# OC_PROT.net
KiCad netlist of a schematic drawn in Altium Designer
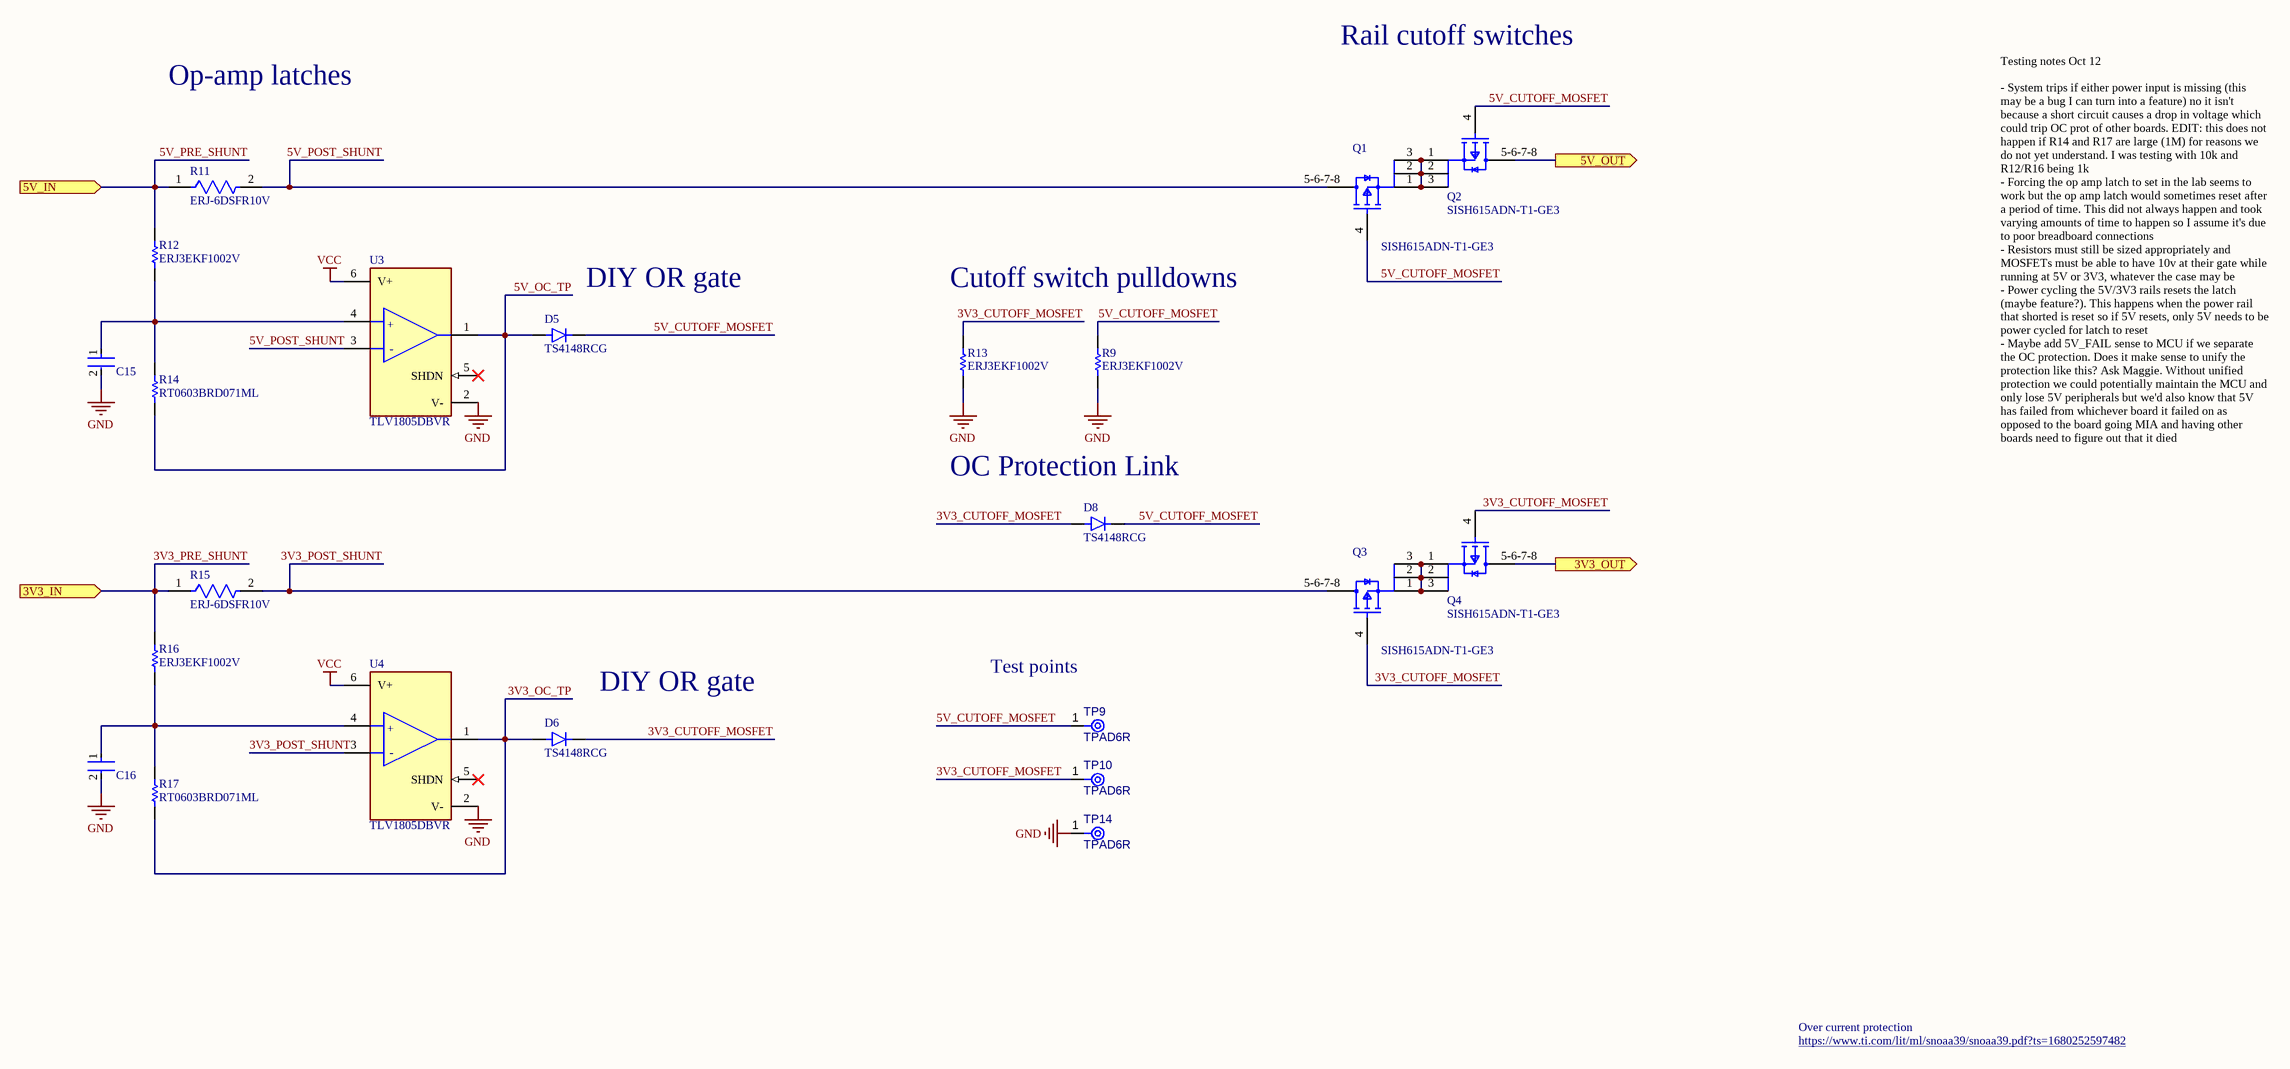
[diagram p0: OC_PROT.SchDoc]

(export (version "E")
  (design (tool "Eeschema 10.0.6"))
  (components
    (comp (ref "C15")
      (value "C0402C104K8PACTU")
      (footprint "FP-C0402-BB-MFG")
      (description "CAP CER 0.1UF 10V X5R 0402")
      (fields (field (name "MANUFACTURER") "Kemet") (field (name "TOLERANCE") "0.1"))
      (libsource (lib "Altium Content Vault") (part "b4654b650e69147ec39a6b967a45e02"))
    )
    (comp (ref "C16")
      (value "C0402C104K8PACTU")
      (footprint "FP-C0402-BB-MFG")
      (description "CAP CER 0.1UF 10V X5R 0402")
      (fields (field (name "MANUFACTURER") "Kemet") (field (name "TOLERANCE") "0.1"))
      (libsource (lib "Altium Content Vault") (part "b4654b650e69147ec39a6b967a45e02"))
    )
    (comp (ref "D5")
      (value "TS4148RCG")
      (footprint "TS4148RCG-Footprint-1")
      (description "SMD Si-Diode 75V 100mA 0603")
      (libsource (lib "uORocketry Hardware") (part "TS4148RCG"))
    )
    (comp (ref "D6")
      (value "TS4148RCG")
      (footprint "TS4148RCG-Footprint-1")
      (description "SMD Si-Diode 75V 100mA 0603")
      (libsource (lib "uORocketry Hardware") (part "TS4148RCG"))
    )
    (comp (ref "D8")
      (value "TS4148RCG")
      (footprint "TS4148RCG-Footprint-1")
      (description "SMD Si-Diode 75V 100mA 0603")
      (libsource (lib "uORocketry Hardware") (part "TS4148RCG"))
    )
    (comp (ref "Q1")
      (value "SISH615ADN-T1-GE3")
      (footprint "SISH615ADN-T1-GE3-Footprint-1")
      (description "Trans MOSFET P-CH 20V 22.1A 8-Pin PowerPAK 1212 EP T/R")
      (libsource (lib "uORocketry Hardware") (part "SISH615ADN-T1-GE3-Symbol-1"))
    )
    (comp (ref "Q2")
      (value "SISH615ADN-T1-GE3")
      (footprint "SISH615ADN-T1-GE3-Footprint-1")
      (description "Trans MOSFET P-CH 20V 22.1A 8-Pin PowerPAK 1212 EP T/R")
      (libsource (lib "uORocketry Hardware") (part "SISH615ADN-T1-GE3-Symbol-1"))
    )
    (comp (ref "Q3")
      (value "SISH615ADN-T1-GE3")
      (footprint "SISH615ADN-T1-GE3-Footprint-1")
      (description "Trans MOSFET P-CH 20V 22.1A 8-Pin PowerPAK 1212 EP T/R")
      (libsource (lib "uORocketry Hardware") (part "SISH615ADN-T1-GE3-Symbol-1"))
    )
    (comp (ref "Q4")
      (value "SISH615ADN-T1-GE3")
      (footprint "SISH615ADN-T1-GE3-Footprint-1")
      (description "Trans MOSFET P-CH 20V 22.1A 8-Pin PowerPAK 1212 EP T/R")
      (libsource (lib "uORocketry Hardware") (part "SISH615ADN-T1-GE3-Symbol-1"))
    )
    (comp (ref "R9")
      (value "ERJ3EKF1002V")
      (footprint "RESC1609X55X30LL15T15")
      (description "Chip Resistor, 10 KOhm, +/- 1%, 0.1 W, -55 to 155 degC, 0603 (1608 Metric), RoHS, Tape and Reel")
      (fields (field (name "TOLERANCE") "1%") (field (name "MANUFACTURER") "Panasonic"))
      (libsource (lib "Altium Content Vault") (part "RES-2"))
    )
    (comp (ref "R11")
      (value "ERJ-6DSFR10V")
      (footprint "FP-ERJ6D-MFG")
      (description "RES 0.1 OHM 1% 1/2W 0805")
      (fields (field (name "TOLERANCE") "1%"))
      (libsource (lib "Altium Content Vault") (part "1029c3af85768c4190bb7ad29bc67b5"))
    )
    (comp (ref "R12")
      (value "ERJ3EKF1002V")
      (footprint "RESC1609X55X30LL15T15")
      (description "Chip Resistor, 10 KOhm, +/- 1%, 0.1 W, -55 to 155 degC, 0603 (1608 Metric), RoHS, Tape and Reel")
      (fields (field (name "TOLERANCE") "1%") (field (name "MANUFACTURER") "Panasonic"))
      (libsource (lib "Altium Content Vault") (part "RES-2"))
    )
    (comp (ref "R13")
      (value "ERJ3EKF1002V")
      (footprint "RESC1609X55X30LL15T15")
      (description "Chip Resistor, 10 KOhm, +/- 1%, 0.1 W, -55 to 155 degC, 0603 (1608 Metric), RoHS, Tape and Reel")
      (fields (field (name "TOLERANCE") "1%") (field (name "MANUFACTURER") "Panasonic"))
      (libsource (lib "Altium Content Vault") (part "RES-2"))
    )
    (comp (ref "R14")
      (value "RT0603BRD071ML")
      (footprint "RESC1608X55X30NL20T20")
      (fields (field (name "MANUFACTURER") "Panasonic") (field (name "PART NUMBER") "ERA-3AEB163V"))
      (libsource (lib "Altium Content Vault") (part "RES"))
    )
    (comp (ref "R15")
      (value "ERJ-6DSFR10V")
      (footprint "FP-ERJ6D-MFG")
      (description "RES 0.1 OHM 1% 1/2W 0805")
      (fields (field (name "TOLERANCE") "1%"))
      (libsource (lib "Altium Content Vault") (part "1029c3af85768c4190bb7ad29bc67b5"))
    )
    (comp (ref "R16")
      (value "ERJ3EKF1002V")
      (footprint "RESC1609X55X30LL15T15")
      (description "Chip Resistor, 10 KOhm, +/- 1%, 0.1 W, -55 to 155 degC, 0603 (1608 Metric), RoHS, Tape and Reel")
      (fields (field (name "TOLERANCE") "1%") (field (name "MANUFACTURER") "Panasonic"))
      (libsource (lib "Altium Content Vault") (part "RES-2"))
    )
    (comp (ref "R17")
      (value "RT0603BRD071ML")
      (footprint "RESC1608X55X30NL20T20")
      (fields (field (name "MANUFACTURER") "Panasonic") (field (name "PART NUMBER") "ERA-3AEB163V"))
      (libsource (lib "Altium Content Vault") (part "RES"))
    )
    (comp (ref "TP9")
      (value "TPAD6R")
      (footprint "TP06R")
      (description "0.6mm round")
      (libsource (lib "uORocketry Hardware") (part "CMP-001-0001-4"))
    )
    (comp (ref "TP10")
      (value "TPAD6R")
      (footprint "TP06R")
      (description "0.6mm round")
      (libsource (lib "uORocketry Hardware") (part "CMP-001-0001-4"))
    )
    (comp (ref "TP14")
      (value "TPAD6R")
      (footprint "TP06R")
      (description "0.6mm round")
      (libsource (lib "uORocketry Hardware") (part "CMP-001-0001-4"))
    )
    (comp (ref "U3")
      (value "TLV1805DBVR")
      (footprint "FP-DBV0006A-IPC_C")
      (description "40V, RAIL-TO-RAIL INPUT, PUSH-PU")
      (libsource (lib "Altium Content Vault") (part "c7aa3bc3dbf0dc8b0b0354779bd1228"))
    )
    (comp (ref "U4")
      (value "TLV1805DBVR")
      (footprint "FP-DBV0006A-IPC_C")
      (description "40V, RAIL-TO-RAIL INPUT, PUSH-PU")
      (libsource (lib "Altium Content Vault") (part "c7aa3bc3dbf0dc8b0b0354779bd1228"))
    )
  )
  (nets
    (net (code "1") (name "/3V3_CUTOFF_MOSFET") (class "Default")
      (node (ref "D6") (pin "C") (pinfunction "K_C") (pintype "passive"))
      (node (ref "D8") (pin "A") (pinfunction "A_A") (pintype "passive"))
      (node (ref "Q3") (pin "4") (pinfunction "G_4") (pintype "passive"))
      (node (ref "Q4") (pin "4") (pinfunction "G_4") (pintype "passive"))
      (node (ref "R13") (pin "2") (pinfunction "2_2") (pintype "passive"))
      (node (ref "TP10") (pin "1") (pinfunction "TP_1") (pintype "passive"))
    )
    (net (code "2") (name "/3V3_OC_TP") (class "Default")
      (node (ref "D6") (pin "A") (pinfunction "A_A") (pintype "passive"))
      (node (ref "R17") (pin "1") (pinfunction "1_1") (pintype "passive"))
      (node (ref "U4") (pin "1") (pinfunction "OUT_1") (pintype "passive"))
    )
    (net (code "3") (name "/3V3_OUT") (class "Default")
      (node (ref "Q4") (pin "5-6-7-8") (pinfunction "D_5-6-7-8") (pintype "passive"))
    )
    (net (code "4") (name "/3V3_POST_SHUNT") (class "Default")
      (node (ref "Q3") (pin "5-6-7-8") (pinfunction "D_5-6-7-8") (pintype "passive"))
      (node (ref "R15") (pin "2") (pinfunction "2_2") (pintype "passive"))
      (node (ref "U4") (pin "3") (pinfunction "-IN_3") (pintype "tri_state"))
    )
    (net (code "5") (name "/3V3_PRE_SHUNT") (class "Default")
      (node (ref "R15") (pin "1") (pinfunction "1_1") (pintype "passive"))
      (node (ref "R16") (pin "2") (pinfunction "2_2") (pintype "passive"))
    )
    (net (code "6") (name "/5V_CUTOFF_MOSFET") (class "Default")
      (node (ref "D5") (pin "C") (pinfunction "K_C") (pintype "passive"))
      (node (ref "D8") (pin "C") (pinfunction "K_C") (pintype "passive"))
      (node (ref "Q1") (pin "4") (pinfunction "G_4") (pintype "passive"))
      (node (ref "Q2") (pin "4") (pinfunction "G_4") (pintype "passive"))
      (node (ref "R9") (pin "2") (pinfunction "2_2") (pintype "passive"))
      (node (ref "TP9") (pin "1") (pinfunction "TP_1") (pintype "passive"))
    )
    (net (code "7") (name "/5V_OC_TP") (class "Default")
      (node (ref "D5") (pin "A") (pinfunction "A_A") (pintype "passive"))
      (node (ref "R14") (pin "1") (pinfunction "1_1") (pintype "passive"))
      (node (ref "U3") (pin "1") (pinfunction "OUT_1") (pintype "passive"))
    )
    (net (code "8") (name "/5V_OUT") (class "Default")
      (node (ref "Q2") (pin "5-6-7-8") (pinfunction "D_5-6-7-8") (pintype "passive"))
    )
    (net (code "9") (name "/5V_POST_SHUNT") (class "Default")
      (node (ref "Q1") (pin "5-6-7-8") (pinfunction "D_5-6-7-8") (pintype "passive"))
      (node (ref "R11") (pin "2") (pinfunction "2_2") (pintype "passive"))
      (node (ref "U3") (pin "3") (pinfunction "-IN_3") (pintype "tri_state"))
    )
    (net (code "10") (name "/5V_PRE_SHUNT") (class "Default")
      (node (ref "R11") (pin "1") (pinfunction "1_1") (pintype "passive"))
      (node (ref "R12") (pin "2") (pinfunction "2_2") (pintype "passive"))
    )
    (net (code "11") (name "GND") (class "Default")
      (node (ref "C15") (pin "2") (pinfunction "2_2") (pintype "passive"))
      (node (ref "C16") (pin "2") (pinfunction "2_2") (pintype "passive"))
      (node (ref "R13") (pin "1") (pinfunction "1_1") (pintype "passive"))
      (node (ref "R9") (pin "1") (pinfunction "1_1") (pintype "passive"))
      (node (ref "TP14") (pin "1") (pinfunction "TP_1") (pintype "passive"))
      (node (ref "U3") (pin "2") (pinfunction "V-_2") (pintype "power_in"))
      (node (ref "U4") (pin "2") (pinfunction "V-_2") (pintype "power_in"))
    )
    (net (code "12") (name "Net-(Q1-S-Pad1)") (class "Default")
      (node (ref "Q1") (pin "1") (pinfunction "S_1") (pintype "passive"))
      (node (ref "Q1") (pin "2") (pinfunction "S_2") (pintype "passive"))
      (node (ref "Q1") (pin "3") (pinfunction "S_3") (pintype "passive"))
      (node (ref "Q2") (pin "1") (pinfunction "S_1") (pintype "passive"))
      (node (ref "Q2") (pin "2") (pinfunction "S_2") (pintype "passive"))
      (node (ref "Q2") (pin "3") (pinfunction "S_3") (pintype "passive"))
    )
    (net (code "13") (name "Net-(Q3-S-Pad1)") (class "Default")
      (node (ref "Q3") (pin "1") (pinfunction "S_1") (pintype "passive"))
      (node (ref "Q3") (pin "2") (pinfunction "S_2") (pintype "passive"))
      (node (ref "Q3") (pin "3") (pinfunction "S_3") (pintype "passive"))
      (node (ref "Q4") (pin "1") (pinfunction "S_1") (pintype "passive"))
      (node (ref "Q4") (pin "2") (pinfunction "S_2") (pintype "passive"))
      (node (ref "Q4") (pin "3") (pinfunction "S_3") (pintype "passive"))
    )
    (net (code "14") (name "Net-(U3-+IN)") (class "Default")
      (node (ref "C15") (pin "1") (pinfunction "1_1") (pintype "passive"))
      (node (ref "R12") (pin "1") (pinfunction "1_1") (pintype "passive"))
      (node (ref "R14") (pin "2") (pinfunction "2_2") (pintype "passive"))
      (node (ref "U3") (pin "4") (pinfunction "+IN_4") (pintype "tri_state"))
    )
    (net (code "15") (name "Net-(U4-+IN)") (class "Default")
      (node (ref "C16") (pin "1") (pinfunction "1_1") (pintype "passive"))
      (node (ref "R16") (pin "1") (pinfunction "1_1") (pintype "passive"))
      (node (ref "R17") (pin "2") (pinfunction "2_2") (pintype "passive"))
      (node (ref "U4") (pin "4") (pinfunction "+IN_4") (pintype "tri_state"))
    )
    (net (code "16") (name "VCC") (class "Default")
      (node (ref "U3") (pin "6") (pinfunction "V+_6") (pintype "power_in"))
      (node (ref "U4") (pin "6") (pinfunction "V+_6") (pintype "power_in"))
    )
    (net (code "17") (name "unconnected-(U3-SHDN-Pad5)") (class "Default")
      (node (ref "U3") (pin "5") (pinfunction "SHDN_5") (pintype "input+no_connect"))
    )
    (net (code "18") (name "unconnected-(U4-SHDN-Pad5)") (class "Default")
      (node (ref "U4") (pin "5") (pinfunction "SHDN_5") (pintype "input+no_connect"))
    )
  )
)
